# Transmitter_old.net
KiCad netlist of a schematic drawn in Altium Designer
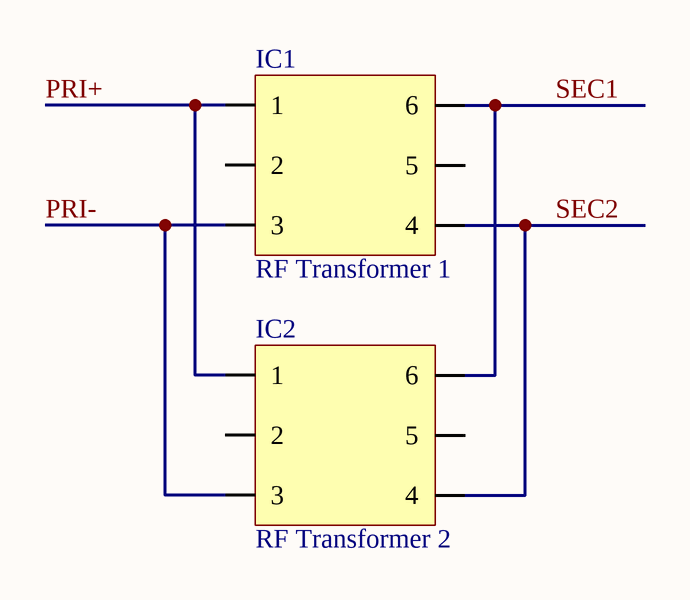
[diagram p0: Transmitter_old.SchDoc]

(export (version "E")
  (design (tool "Eeschema 10.0.6"))
  (components
    (comp (ref "IC1")
      (value "RF Transformer 1")
      (footprint "PWB-X-XL_")
      (libsource (lib "Components") (part "RF Transformer"))
    )
    (comp (ref "IC2")
      (value "RF Transformer 2")
      (footprint "PWB-X-XL_")
      (libsource (lib "Components") (part "RF Transformer"))
    )
  )
  (nets
    (net (code "1") (name "/PRI+") (class "Default")
      (node (ref "IC1") (pin "1") (pinfunction "1_1") (pintype "passive"))
      (node (ref "IC2") (pin "1") (pinfunction "1_1") (pintype "passive"))
    )
    (net (code "2") (name "/PRI-") (class "Default")
      (node (ref "IC1") (pin "3") (pinfunction "3_3") (pintype "passive"))
      (node (ref "IC2") (pin "3") (pinfunction "3_3") (pintype "passive"))
    )
    (net (code "3") (name "/SEC1") (class "Default")
      (node (ref "IC1") (pin "6") (pinfunction "6_6") (pintype "passive"))
      (node (ref "IC2") (pin "6") (pinfunction "6_6") (pintype "passive"))
    )
    (net (code "4") (name "/SEC2") (class "Default")
      (node (ref "IC1") (pin "4") (pinfunction "4_4") (pintype "passive"))
      (node (ref "IC2") (pin "4") (pinfunction "4_4") (pintype "passive"))
    )
    (net (code "5") (name "unconnected-(IC1-Pad2)") (class "Default")
      (node (ref "IC1") (pin "2") (pinfunction "2_2") (pintype "passive"))
    )
    (net (code "6") (name "unconnected-(IC1-Pad5)") (class "Default")
      (node (ref "IC1") (pin "5") (pinfunction "5_5") (pintype "passive"))
    )
    (net (code "7") (name "unconnected-(IC2-Pad2)") (class "Default")
      (node (ref "IC2") (pin "2") (pinfunction "2_2") (pintype "passive"))
    )
    (net (code "8") (name "unconnected-(IC2-Pad5)") (class "Default")
      (node (ref "IC2") (pin "5") (pinfunction "5_5") (pintype "passive"))
    )
  )
)
